# 5R_Supply.net
KiCad netlist of a schematic drawn in Altium Designer
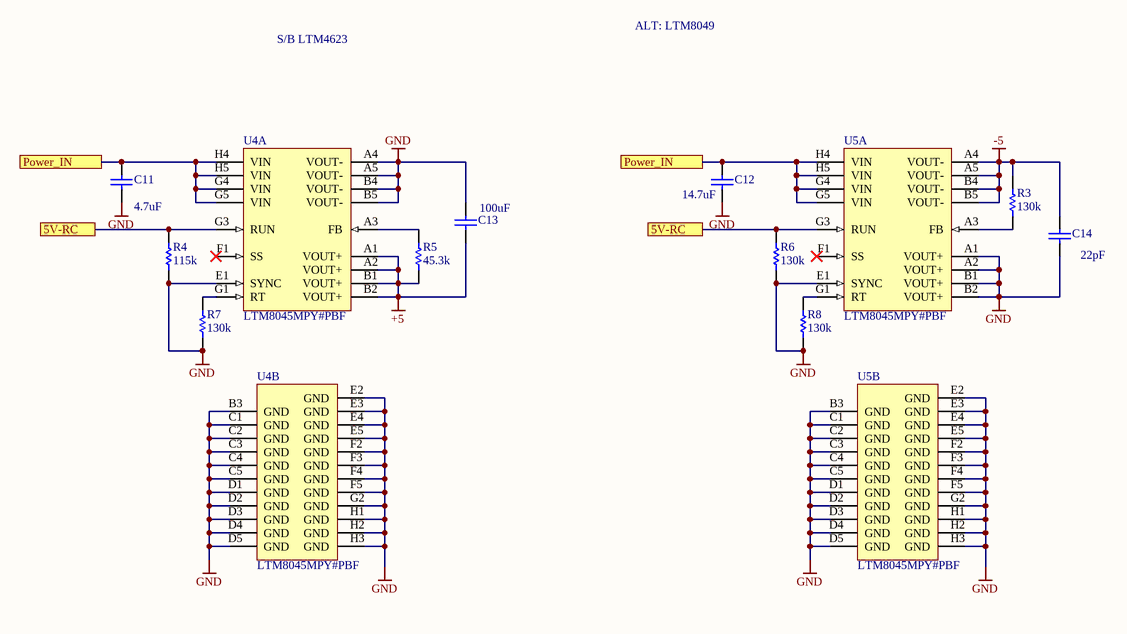
[diagram p0: 5R_Supply.SchDoc]

(export (version "E")
  (design (tool "Eeschema 10.0.6"))
  (components
    (comp (ref "C11")
      (value "4.7uF")
      (footprint "CAPC1206(3216)110_N")
      (libsource (lib "Altium Content Vault") (part "CMP-1037-04332-1"))
    )
    (comp (ref "C12")
      (value "CAP CER 10UF 6.3V X5R 1206")
      (footprint "CAPC1206(3216)130_N")
      (fields
        (field (name "MANUFACTURER") "Taiyo Yuden")
        (field (name "MANUFACTURER PART NUMBER") "JMK316BJ106ML-T")
        (field (name "TOLERANCE") "±20%")
        (field (name "CAPACITANCE") "14.7uF")
      )
      (libsource (lib "Altium Content Vault") (part "CMP-1037-04913-1"))
    )
    (comp (ref "C13")
      (value "100uF")
      (footprint "CAPC1210(3225)100_N")
      (libsource (lib "Altium Content Vault") (part "CMP-1038-01331-1"))
    )
    (comp (ref "C14")
      (value "CAP CER 10UF 6.3V X5R 1206")
      (footprint "CAPC1206(3216)130_N")
      (fields
        (field (name "MANUFACTURER") "Taiyo Yuden")
        (field (name "MANUFACTURER PART NUMBER") "JMK316BJ106ML-T")
        (field (name "TOLERANCE") "±20%")
        (field (name "CAPACITANCE") "22pF")
      )
      (libsource (lib "Altium Content Vault") (part "CMP-1037-04913-1"))
    )
    (comp (ref "R3")
      (value "RES SMD 43K OHM 1% 1/8W 0805")
      (footprint "RESC0805(2012)_M")
      (description "RES SMD 10K OHM 1% 1/8W 0805")
      (fields (field (name "RESISTANCE (OHMS)") "130k"))
      (libsource (lib "Altium Content Vault") (part "CMP-1013-00017-1"))
    )
    (comp (ref "R4")
      (value "RES SMD 43K OHM 1% 1/8W 0805")
      (footprint "RESC0805(2012)_M")
      (description "RES SMD 10K OHM 1% 1/8W 0805")
      (fields (field (name "RESISTANCE (OHMS)") "115k"))
      (libsource (lib "Altium Content Vault") (part "CMP-1013-00017-1"))
    )
    (comp (ref "R5")
      (value "~")
      (footprint "RESC0805(2012)_M")
      (fields (field (name "RESISTANCE (OHMS)") "45.3k"))
      (libsource (lib "Altium Content Vault") (part "CMP-1013-00017-1"))
    )
    (comp (ref "R6")
      (value "RES SMD 43K OHM 1% 1/8W 0805")
      (footprint "RESC0805(2012)_M")
      (description "RES SMD 10K OHM 1% 1/8W 0805")
      (fields (field (name "RESISTANCE (OHMS)") "130k"))
      (libsource (lib "Altium Content Vault") (part "CMP-1013-00017-1"))
    )
    (comp (ref "R7")
      (value "RES SMD 43K OHM 1% 1/8W 0805")
      (footprint "RESC0805(2012)_M")
      (description "RES SMD 10K OHM 1% 1/8W 0805")
      (fields (field (name "RESISTANCE (OHMS)") "130k"))
      (libsource (lib "Altium Content Vault") (part "CMP-1013-00017-1"))
    )
    (comp (ref "R8")
      (value "RES SMD 43K OHM 1% 1/8W 0805")
      (footprint "RESC0805(2012)_M")
      (description "RES SMD 10K OHM 1% 1/8W 0805")
      (fields (field (name "RESISTANCE (OHMS)") "130k"))
      (libsource (lib "Altium Content Vault") (part "CMP-1013-00017-1"))
    )
    (comp (ref "U4")
      (value "LTM8045MPY#PBF")
      (footprint "LT-BGA-40-11250X6250X4920")
      (fields (field (name "MANUFACTURER") "Linear Technology"))
      (libsource (lib "Altium Content Vault") (part "LT-LTM8045-BGA-40"))
    )
    (comp (ref "U5")
      (value "LTM8045MPY#PBF")
      (footprint "LT-BGA-40-11250X6250X4920")
      (fields (field (name "MANUFACTURER") "Linear Technology"))
      (libsource (lib "Altium Content Vault") (part "LT-LTM8045-BGA-40"))
    )
  )
  (nets
    (net (code "1") (name "+5") (class "Default")
      (node (ref "C13") (pin "1") (pinfunction "1_1") (pintype "passive"))
      (node (ref "R5") (pin "1") (pinfunction "1_1") (pintype "passive"))
      (node (ref "U4") (pin "A1") (pinfunction "VOUT+_A1") (pintype "power_in"))
      (node (ref "U4") (pin "A2") (pinfunction "VOUT+_A2") (pintype "power_in"))
      (node (ref "U4") (pin "B1") (pinfunction "VOUT+_B1") (pintype "power_in"))
      (node (ref "U4") (pin "B2") (pinfunction "VOUT+_B2") (pintype "power_in"))
    )
    (net (code "2") (name "-5") (class "Default")
      (node (ref "C14") (pin "2") (pinfunction "2_2") (pintype "passive"))
      (node (ref "R3") (pin "2") (pinfunction "2_2") (pintype "passive"))
      (node (ref "U5") (pin "A4") (pinfunction "VOUT-_A4") (pintype "power_in"))
      (node (ref "U5") (pin "A5") (pinfunction "VOUT-_A5") (pintype "power_in"))
      (node (ref "U5") (pin "B4") (pinfunction "VOUT-_B4") (pintype "power_in"))
      (node (ref "U5") (pin "B5") (pinfunction "VOUT-_B5") (pintype "power_in"))
    )
    (net (code "3") (name "/5V-RC") (class "Default")
      (node (ref "R4") (pin "2") (pinfunction "2_2") (pintype "passive"))
      (node (ref "R6") (pin "2") (pinfunction "2_2") (pintype "passive"))
      (node (ref "U4") (pin "G3") (pinfunction "RUN_G3") (pintype "input"))
      (node (ref "U5") (pin "G3") (pinfunction "RUN_G3") (pintype "input"))
    )
    (net (code "4") (name "/Power_IN") (class "Default")
      (node (ref "C11") (pin "2") (pinfunction "2_2") (pintype "passive"))
      (node (ref "C12") (pin "2") (pinfunction "2_2") (pintype "passive"))
      (node (ref "U4") (pin "G4") (pinfunction "VIN_G4") (pintype "power_in"))
      (node (ref "U4") (pin "G5") (pinfunction "VIN_G5") (pintype "power_in"))
      (node (ref "U4") (pin "H4") (pinfunction "VIN_H4") (pintype "power_in"))
      (node (ref "U4") (pin "H5") (pinfunction "VIN_H5") (pintype "power_in"))
      (node (ref "U5") (pin "G4") (pinfunction "VIN_G4") (pintype "power_in"))
      (node (ref "U5") (pin "G5") (pinfunction "VIN_G5") (pintype "power_in"))
      (node (ref "U5") (pin "H4") (pinfunction "VIN_H4") (pintype "power_in"))
      (node (ref "U5") (pin "H5") (pinfunction "VIN_H5") (pintype "power_in"))
    )
    (net (code "5") (name "GND") (class "Default")
      (node (ref "C11") (pin "1") (pinfunction "1_1") (pintype "passive"))
      (node (ref "C12") (pin "1") (pinfunction "1_1") (pintype "passive"))
      (node (ref "C13") (pin "2") (pinfunction "2_2") (pintype "passive"))
      (node (ref "C14") (pin "1") (pinfunction "1_1") (pintype "passive"))
      (node (ref "R4") (pin "1") (pinfunction "1_1") (pintype "passive"))
      (node (ref "R6") (pin "1") (pinfunction "1_1") (pintype "passive"))
      (node (ref "R7") (pin "1") (pinfunction "1_1") (pintype "passive"))
      (node (ref "R8") (pin "1") (pinfunction "1_1") (pintype "passive"))
      (node (ref "U4") (pin "A4") (pinfunction "VOUT-_A4") (pintype "power_in"))
      (node (ref "U4") (pin "A5") (pinfunction "VOUT-_A5") (pintype "power_in"))
      (node (ref "U4") (pin "B3") (pinfunction "GND_B3") (pintype "power_in"))
      (node (ref "U4") (pin "B4") (pinfunction "VOUT-_B4") (pintype "power_in"))
      (node (ref "U4") (pin "B5") (pinfunction "VOUT-_B5") (pintype "power_in"))
      (node (ref "U4") (pin "C1") (pinfunction "GND_C1") (pintype "power_in"))
      (node (ref "U4") (pin "C2") (pinfunction "GND_C2") (pintype "power_in"))
      (node (ref "U4") (pin "C3") (pinfunction "GND_C3") (pintype "power_in"))
      (node (ref "U4") (pin "C4") (pinfunction "GND_C4") (pintype "power_in"))
      (node (ref "U4") (pin "C5") (pinfunction "GND_C5") (pintype "power_in"))
      (node (ref "U4") (pin "D1") (pinfunction "GND_D1") (pintype "power_in"))
      (node (ref "U4") (pin "D2") (pinfunction "GND_D2") (pintype "power_in"))
      (node (ref "U4") (pin "D3") (pinfunction "GND_D3") (pintype "power_in"))
      (node (ref "U4") (pin "D4") (pinfunction "GND_D4") (pintype "power_in"))
      (node (ref "U4") (pin "D5") (pinfunction "GND_D5") (pintype "power_in"))
      (node (ref "U4") (pin "E1") (pinfunction "SYNC_E1") (pintype "input"))
      (node (ref "U4") (pin "E2") (pinfunction "GND_E2") (pintype "power_in"))
      (node (ref "U4") (pin "E3") (pinfunction "GND_E3") (pintype "power_in"))
      (node (ref "U4") (pin "E4") (pinfunction "GND_E4") (pintype "power_in"))
      (node (ref "U4") (pin "E5") (pinfunction "GND_E5") (pintype "power_in"))
      (node (ref "U4") (pin "F2") (pinfunction "GND_F2") (pintype "power_in"))
      (node (ref "U4") (pin "F3") (pinfunction "GND_F3") (pintype "power_in"))
      (node (ref "U4") (pin "F4") (pinfunction "GND_F4") (pintype "power_in"))
      (node (ref "U4") (pin "F5") (pinfunction "GND_F5") (pintype "power_in"))
      (node (ref "U4") (pin "G2") (pinfunction "GND_G2") (pintype "power_in"))
      (node (ref "U4") (pin "H1") (pinfunction "GND_H1") (pintype "power_in"))
      (node (ref "U4") (pin "H2") (pinfunction "GND_H2") (pintype "power_in"))
      (node (ref "U4") (pin "H3") (pinfunction "GND_H3") (pintype "power_in"))
      (node (ref "U5") (pin "A1") (pinfunction "VOUT+_A1") (pintype "power_in"))
      (node (ref "U5") (pin "A2") (pinfunction "VOUT+_A2") (pintype "power_in"))
      (node (ref "U5") (pin "B1") (pinfunction "VOUT+_B1") (pintype "power_in"))
      (node (ref "U5") (pin "B2") (pinfunction "VOUT+_B2") (pintype "power_in"))
      (node (ref "U5") (pin "B3") (pinfunction "GND_B3") (pintype "power_in"))
      (node (ref "U5") (pin "C1") (pinfunction "GND_C1") (pintype "power_in"))
      (node (ref "U5") (pin "C2") (pinfunction "GND_C2") (pintype "power_in"))
      (node (ref "U5") (pin "C3") (pinfunction "GND_C3") (pintype "power_in"))
      (node (ref "U5") (pin "C4") (pinfunction "GND_C4") (pintype "power_in"))
      (node (ref "U5") (pin "C5") (pinfunction "GND_C5") (pintype "power_in"))
      (node (ref "U5") (pin "D1") (pinfunction "GND_D1") (pintype "power_in"))
      (node (ref "U5") (pin "D2") (pinfunction "GND_D2") (pintype "power_in"))
      (node (ref "U5") (pin "D3") (pinfunction "GND_D3") (pintype "power_in"))
      (node (ref "U5") (pin "D4") (pinfunction "GND_D4") (pintype "power_in"))
      (node (ref "U5") (pin "D5") (pinfunction "GND_D5") (pintype "power_in"))
      (node (ref "U5") (pin "E1") (pinfunction "SYNC_E1") (pintype "input"))
      (node (ref "U5") (pin "E2") (pinfunction "GND_E2") (pintype "power_in"))
      (node (ref "U5") (pin "E3") (pinfunction "GND_E3") (pintype "power_in"))
      (node (ref "U5") (pin "E4") (pinfunction "GND_E4") (pintype "power_in"))
      (node (ref "U5") (pin "E5") (pinfunction "GND_E5") (pintype "power_in"))
      (node (ref "U5") (pin "F2") (pinfunction "GND_F2") (pintype "power_in"))
      (node (ref "U5") (pin "F3") (pinfunction "GND_F3") (pintype "power_in"))
      (node (ref "U5") (pin "F4") (pinfunction "GND_F4") (pintype "power_in"))
      (node (ref "U5") (pin "F5") (pinfunction "GND_F5") (pintype "power_in"))
      (node (ref "U5") (pin "G2") (pinfunction "GND_G2") (pintype "power_in"))
      (node (ref "U5") (pin "H1") (pinfunction "GND_H1") (pintype "power_in"))
      (node (ref "U5") (pin "H2") (pinfunction "GND_H2") (pintype "power_in"))
      (node (ref "U5") (pin "H3") (pinfunction "GND_H3") (pintype "power_in"))
    )
    (net (code "6") (name "Net-(U4A-FB)") (class "Default")
      (node (ref "R5") (pin "2") (pinfunction "2_2") (pintype "passive"))
      (node (ref "U4") (pin "A3") (pinfunction "FB_A3") (pintype "input"))
    )
    (net (code "7") (name "Net-(U4A-RT)") (class "Default")
      (node (ref "R7") (pin "2") (pinfunction "2_2") (pintype "passive"))
      (node (ref "U4") (pin "G1") (pinfunction "RT_G1") (pintype "input"))
    )
    (net (code "8") (name "Net-(U5A-FB)") (class "Default")
      (node (ref "R3") (pin "1") (pinfunction "1_1") (pintype "passive"))
      (node (ref "U5") (pin "A3") (pinfunction "FB_A3") (pintype "input"))
    )
    (net (code "9") (name "Net-(U5A-RT)") (class "Default")
      (node (ref "R8") (pin "2") (pinfunction "2_2") (pintype "passive"))
      (node (ref "U5") (pin "G1") (pinfunction "RT_G1") (pintype "input"))
    )
    (net (code "10") (name "unconnected-(U4A-SS-PadF1)") (class "Default")
      (node (ref "U4") (pin "F1") (pinfunction "SS_F1") (pintype "input+no_connect"))
    )
    (net (code "11") (name "unconnected-(U5A-SS-PadF1)") (class "Default")
      (node (ref "U5") (pin "F1") (pinfunction "SS_F1") (pintype "input+no_connect"))
    )
  )
)
